# Simple-Charger-LiIon-OpampBased-LM324-pr.net
KiCad netlist of a schematic drawn in EAGLE
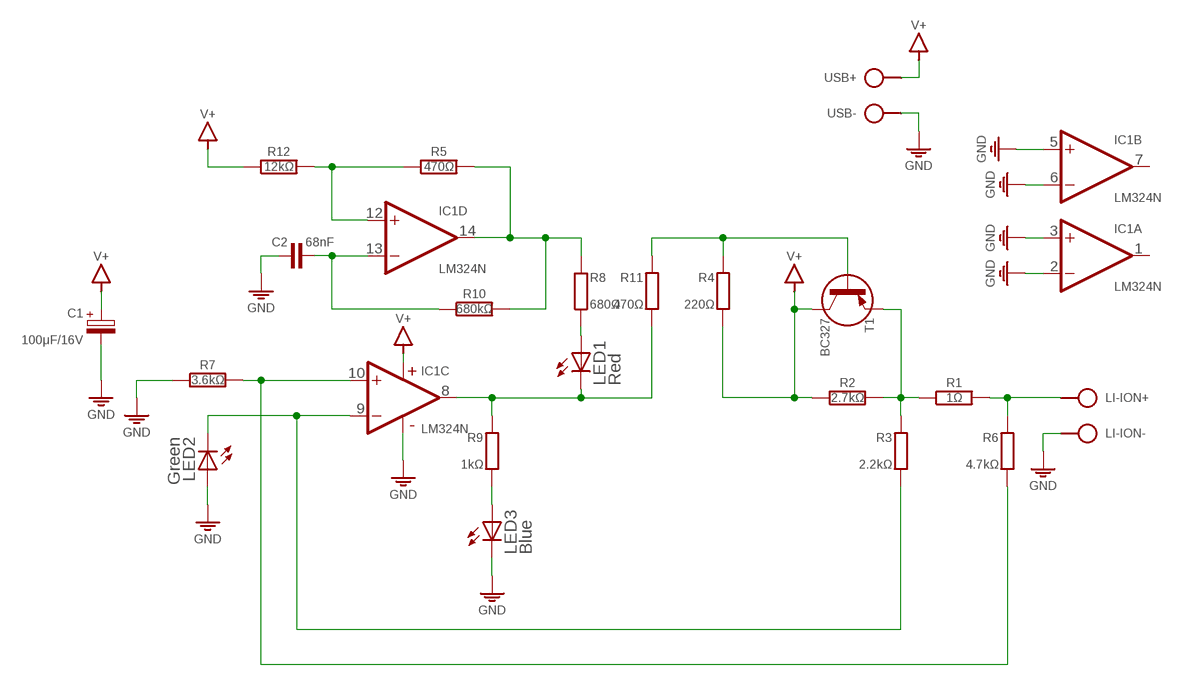
[diagram p0: schematic, sheet 1]

(export (version "E")
  (design (tool "Eeschema 10.0.6"))
  (components
    (comp (ref "C1")
      (value "100μF/16V")
      (footprint "eagle-import:E2,5-5_V")
      (libsource (lib "eagle-import") (part "CPOLE2,5-5/V"))
    )
    (comp (ref "C2")
      (value "68nF")
      (footprint "eagle-import:C050-020X044_V")
      (libsource (lib "eagle-import") (part "C-H050-020X044/V"))
    )
    (comp (ref "IC1")
      (value "LM324N")
      (footprint "eagle-import:DIL14")
      (libsource (lib "eagle-import") (part "LM324N"))
    )
    (comp (ref "LED1")
      (value "Red")
      (footprint "eagle-import:LED3MM")
      (libsource (lib "eagle-import") (part "LED3MM"))
    )
    (comp (ref "LED2")
      (value "Green")
      (footprint "eagle-import:LED3MM")
      (libsource (lib "eagle-import") (part "LED3MM"))
    )
    (comp (ref "LED3")
      (value "Blue")
      (footprint "eagle-import:LED3MM")
      (libsource (lib "eagle-import") (part "LED3MM"))
    )
    (comp (ref "LI-ION")
      (value "SPAD+-+-")
      (footprint "eagle-import:SPAD+-")
      (libsource (lib "eagle-import") (part "SPAD+-+-"))
    )
    (comp (ref "R1")
      (value "1Ω")
      (footprint "eagle-import:0204_10-V")
      (libsource (lib "eagle-import") (part "R-H0204/10-V"))
    )
    (comp (ref "R2")
      (value "2.7kΩ")
      (footprint "eagle-import:0204_10-V")
      (libsource (lib "eagle-import") (part "R-H0204/10-V"))
    )
    (comp (ref "R3")
      (value "2.2kΩ")
      (footprint "eagle-import:0204_10-V")
      (libsource (lib "eagle-import") (part "R0204/10-V"))
    )
    (comp (ref "R4")
      (value "220Ω")
      (footprint "eagle-import:0204_10")
      (libsource (lib "eagle-import") (part "R0204/10"))
    )
    (comp (ref "R5")
      (value "470Ω")
      (footprint "eagle-import:0204_10")
      (libsource (lib "eagle-import") (part "R-H0204/10"))
    )
    (comp (ref "R6")
      (value "4.7kΩ")
      (footprint "eagle-import:0204_10-V")
      (libsource (lib "eagle-import") (part "R0204/10-V"))
    )
    (comp (ref "R7")
      (value "3.6kΩ")
      (footprint "eagle-import:0204_10-V")
      (libsource (lib "eagle-import") (part "R-H0204/10-V"))
    )
    (comp (ref "R8")
      (value "680Ω")
      (footprint "eagle-import:0204_10")
      (libsource (lib "eagle-import") (part "R0204/10"))
    )
    (comp (ref "R9")
      (value "1kΩ")
      (footprint "eagle-import:0204_10-V")
      (libsource (lib "eagle-import") (part "R0204/10-V"))
    )
    (comp (ref "R10")
      (value "680kΩ")
      (footprint "eagle-import:0204_2V")
      (libsource (lib "eagle-import") (part "R-H0204/2V"))
    )
    (comp (ref "R11")
      (value "470Ω")
      (footprint "eagle-import:0204_10-V")
      (libsource (lib "eagle-import") (part "R0204/10-V"))
    )
    (comp (ref "R12")
      (value "12kΩ")
      (footprint "eagle-import:0204_10-V")
      (libsource (lib "eagle-import") (part "R-H0204/10-V"))
    )
    (comp (ref "T1")
      (value "BC327")
      (footprint "eagle-import:TO92")
      (libsource (lib "eagle-import") (part "BC327"))
    )
    (comp (ref "USB")
      (value "SPAD+--+")
      (footprint "eagle-import:SPAD-+")
      (libsource (lib "eagle-import") (part "SPAD+--+"))
    )
  )
  (nets
    (net (code "1") (name "GND") (class "Default")
      (node (ref "C1") (pin "-") (pinfunction "-_-") (pintype "passive"))
      (node (ref "C2") (pin "1") (pinfunction "1_1") (pintype "passive"))
      (node (ref "IC1") (pin "11") (pinfunction "V-_11") (pintype "power_in"))
      (node (ref "IC1") (pin "2") (pinfunction "-IN_2") (pintype "input"))
      (node (ref "IC1") (pin "3") (pinfunction "+IN_3") (pintype "input"))
      (node (ref "IC1") (pin "5") (pinfunction "+IN_5") (pintype "input"))
      (node (ref "IC1") (pin "6") (pinfunction "-IN_6") (pintype "input"))
      (node (ref "LED2") (pin "A") (pinfunction "A_A") (pintype "passive"))
      (node (ref "LED3") (pin "K") (pinfunction "C_K") (pintype "passive"))
      (node (ref "LI-ION") (pin "1") (pinfunction "P$1_1") (pintype "passive"))
      (node (ref "R7") (pin "1") (pinfunction "1_1") (pintype "passive"))
      (node (ref "USB") (pin "1") (pinfunction "P$1_1") (pintype "passive"))
    )
    (net (code "2") (name "Net-(IC1C-+IN)") (class "Default")
      (node (ref "IC1") (pin "10") (pinfunction "+IN_10") (pintype "input"))
      (node (ref "R6") (pin "2") (pinfunction "2_2") (pintype "passive"))
      (node (ref "R7") (pin "2") (pinfunction "2_2") (pintype "passive"))
    )
    (net (code "3") (name "Net-(IC1C--IN)") (class "Default")
      (node (ref "IC1") (pin "9") (pinfunction "-IN_9") (pintype "input"))
      (node (ref "LED2") (pin "K") (pinfunction "C_K") (pintype "passive"))
      (node (ref "R3") (pin "2") (pinfunction "2_2") (pintype "passive"))
    )
    (net (code "4") (name "Net-(IC1C-OUT)") (class "Default")
      (node (ref "IC1") (pin "8") (pinfunction "OUT_8") (pintype "output"))
      (node (ref "LED1") (pin "K") (pinfunction "C_K") (pintype "passive"))
      (node (ref "R11") (pin "2") (pinfunction "2_2") (pintype "passive"))
      (node (ref "R9") (pin "1") (pinfunction "1_1") (pintype "passive"))
    )
    (net (code "5") (name "Net-(IC1D-+IN)") (class "Default")
      (node (ref "IC1") (pin "12") (pinfunction "+IN_12") (pintype "input"))
      (node (ref "R12") (pin "2") (pinfunction "2_2") (pintype "passive"))
      (node (ref "R5") (pin "1") (pinfunction "1_1") (pintype "passive"))
    )
    (net (code "6") (name "Net-(IC1D--IN)") (class "Default")
      (node (ref "C2") (pin "2") (pinfunction "2_2") (pintype "passive"))
      (node (ref "IC1") (pin "13") (pinfunction "-IN_13") (pintype "input"))
      (node (ref "R10") (pin "1") (pinfunction "1_1") (pintype "passive"))
    )
    (net (code "7") (name "Net-(IC1D-OUT)") (class "Default")
      (node (ref "IC1") (pin "14") (pinfunction "OUT_14") (pintype "output"))
      (node (ref "R10") (pin "2") (pinfunction "2_2") (pintype "passive"))
      (node (ref "R5") (pin "2") (pinfunction "2_2") (pintype "passive"))
      (node (ref "R8") (pin "1") (pinfunction "1_1") (pintype "passive"))
    )
    (net (code "8") (name "Net-(LED1-PadA)") (class "Default")
      (node (ref "LED1") (pin "A") (pinfunction "A_A") (pintype "passive"))
      (node (ref "R8") (pin "2") (pinfunction "2_2") (pintype "passive"))
    )
    (net (code "9") (name "Net-(LED3-PadA)") (class "Default")
      (node (ref "LED3") (pin "A") (pinfunction "A_A") (pintype "passive"))
      (node (ref "R9") (pin "2") (pinfunction "2_2") (pintype "passive"))
    )
    (net (code "10") (name "Net-(LI-IONA-P$1)") (class "Default")
      (node (ref "LI-ION") (pin "2") (pinfunction "P$1_2") (pintype "passive"))
      (node (ref "R1") (pin "2") (pinfunction "2_2") (pintype "passive"))
      (node (ref "R6") (pin "1") (pinfunction "1_1") (pintype "passive"))
    )
    (net (code "11") (name "Net-(T1-B)") (class "Default")
      (node (ref "R11") (pin "1") (pinfunction "1_1") (pintype "passive"))
      (node (ref "R4") (pin "1") (pinfunction "1_1") (pintype "passive"))
      (node (ref "T1") (pin "2") (pinfunction "B_2") (pintype "passive"))
    )
    (net (code "12") (name "Net-(T1-E)") (class "Default")
      (node (ref "R1") (pin "1") (pinfunction "1_1") (pintype "passive"))
      (node (ref "R2") (pin "2") (pinfunction "2_2") (pintype "passive"))
      (node (ref "R3") (pin "1") (pinfunction "1_1") (pintype "passive"))
      (node (ref "T1") (pin "3") (pinfunction "E_3") (pintype "passive"))
    )
    (net (code "13") (name "V+") (class "Default")
      (node (ref "C1") (pin "+") (pinfunction "+_+") (pintype "passive"))
      (node (ref "IC1") (pin "4") (pinfunction "V+_4") (pintype "power_in"))
      (node (ref "R12") (pin "1") (pinfunction "1_1") (pintype "passive"))
      (node (ref "R2") (pin "1") (pinfunction "1_1") (pintype "passive"))
      (node (ref "R4") (pin "2") (pinfunction "2_2") (pintype "passive"))
      (node (ref "T1") (pin "1") (pinfunction "C_1") (pintype "passive"))
      (node (ref "USB") (pin "2") (pinfunction "P$1_2") (pintype "passive"))
    )
    (net (code "14") (name "unconnected-(IC1A-OUT-Pad1)") (class "Default")
      (node (ref "IC1") (pin "1") (pinfunction "OUT_1") (pintype "output"))
    )
    (net (code "15") (name "unconnected-(IC1B-OUT-Pad7)") (class "Default")
      (node (ref "IC1") (pin "7") (pinfunction "OUT_7") (pintype "output"))
    )
  )
)
